# TS1A.net
KiCad netlist of a schematic drawn in Altium Designer
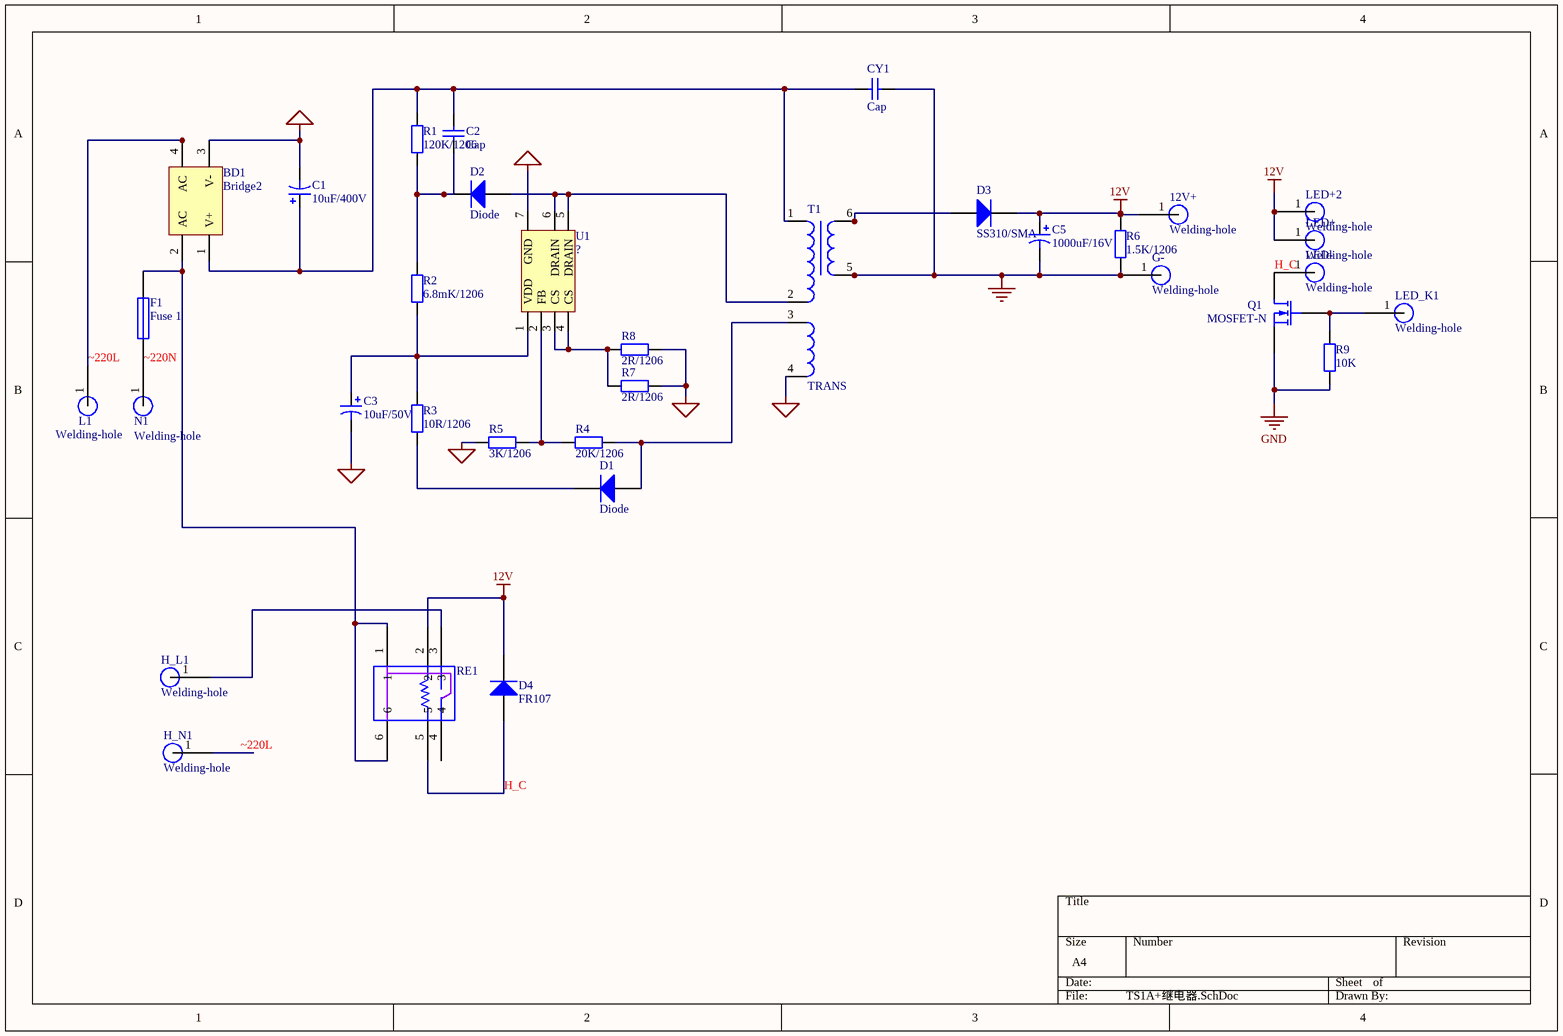
[diagram p0: TS1A+继电器.SchDoc]

(export (version "E")
  (design (tool "Eeschema 10.0.6"))
  (components
    (comp (ref "12V+")
      (value "Welding-hole")
      (footprint "PAD")
      (description "焊接点")
      (libsource (lib "TS_2A") (part "Welding-hole"))
    )
    (comp (ref "BD1")
      (value "Bridge2")
      (footprint "MBL10S")
      (description "Diode Bridge")
      (fields (field (name "PUBLISHER") "Altium Limited"))
      (libsource (lib "Miscellaneous Devices") (part "Bridge2"))
    )
    (comp (ref "C1")
      (value "10uF/400V")
      (footprint "400V/10uF 直插电解电容")
      (description "直插电解电容15uF/400V")
      (fields (field (name "PUBLISHER") "Altium Limited"))
      (libsource (lib "Miscellaneous Devices") (part "Cap Pol1"))
    )
    (comp (ref "C2")
      (value "Cap")
      (footprint "C1206")
      (description "Capacitor")
      (fields (field (name "PUBLISHER") "Altium Limited"))
      (libsource (lib "Miscellaneous Devices") (part "Cap"))
    )
    (comp (ref "C3")
      (value "10uF/50V")
      (footprint "50V/10uF")
      (description "直插电解电容15uF/400V")
      (fields (field (name "PUBLISHER") "Altium Limited"))
      (libsource (lib "Miscellaneous Devices") (part "Cap Pol1"))
    )
    (comp (ref "C5")
      (value "1000uF/16V")
      (footprint "16V/680uF")
      (description "直插电解电容15uF/400V")
      (fields (field (name "PUBLISHER") "Altium Limited"))
      (libsource (lib "Miscellaneous Devices") (part "Cap Pol1"))
    )
    (comp (ref "CY1")
      (value "Cap")
      (footprint "C1206")
      (description "Capacitor")
      (fields (field (name "PUBLISHER") "Altium Limited"))
      (libsource (lib "Miscellaneous Devices") (part "Cap"))
    )
    (comp (ref "D1")
      (value "Diode")
      (footprint "SOD123")
      (description "Default Diode")
      (fields (field (name "PUBLISHER") "Altium Limited"))
      (libsource (lib "Miscellaneous Devices") (part "Diode"))
    )
    (comp (ref "D2")
      (value "Diode")
      (footprint "SOD123")
      (description "Default Diode")
      (fields (field (name "PUBLISHER") "Altium Limited"))
      (libsource (lib "Miscellaneous Devices") (part "Diode"))
    )
    (comp (ref "D3")
      (value "SS310/SMA")
      (footprint "SMA")
      (fields (field (name "PUBLISHER") "Altium Limited"))
      (libsource (lib "Miscellaneous Devices") (part "Diode"))
    )
    (comp (ref "D4")
      (value "FR107")
      (footprint "SOD123")
      (description "Default Diode")
      (fields (field (name "PUBLISHER") "Altium Limited"))
      (libsource (lib "Miscellaneous Devices") (part "Diode"))
    )
    (comp (ref "F1")
      (value "Fuse 1")
      (footprint "FUSE")
      (description "保险丝")
      (fields (field (name "PUBLISHER") "Altium Limited"))
      (libsource (lib "Miscellaneous Devices") (part "Fuse 1"))
    )
    (comp (ref "G-")
      (value "Welding-hole")
      (footprint "PAD")
      (description "焊接点")
      (libsource (lib "TS_2A") (part "Welding-hole"))
    )
    (comp (ref "H_L1")
      (value "Welding-hole")
      (footprint "PAD")
      (description "焊接点")
      (libsource (lib "TS_2A") (part "Welding-hole"))
    )
    (comp (ref "H_N1")
      (value "Welding-hole")
      (footprint "PAD")
      (description "焊接点")
      (libsource (lib "TS_2A") (part "Welding-hole"))
    )
    (comp (ref "L1")
      (value "Welding-hole")
      (footprint "PAD")
      (description "焊接点")
      (libsource (lib "TS_2A") (part "Welding-hole"))
    )
    (comp (ref "LED+")
      (value "Welding-hole")
      (footprint "PAD")
      (description "焊接点")
      (libsource (lib "TS_2A") (part "Welding-hole"))
    )
    (comp (ref "LED+2")
      (value "Welding-hole")
      (footprint "PAD")
      (description "焊接点")
      (libsource (lib "TS_2A") (part "Welding-hole"))
    )
    (comp (ref "LED-")
      (value "Welding-hole")
      (footprint "PAD")
      (description "焊接点")
      (libsource (lib "TS_2A") (part "Welding-hole"))
    )
    (comp (ref "LED_K1")
      (value "Welding-hole")
      (footprint "PAD")
      (description "焊接点")
      (libsource (lib "TS_2A") (part "Welding-hole"))
    )
    (comp (ref "N1")
      (value "Welding-hole")
      (footprint "PAD")
      (description "焊接点")
      (libsource (lib "TS_2A") (part "Welding-hole"))
    )
    (comp (ref "Q1")
      (value "MOSFET-N")
      (footprint "SOT_23_N-MOS")
      (description "N-Channel MOSFET")
      (fields (field (name "PUBLISHER") "Altium Limited"))
      (libsource (lib "Miscellaneous Devices") (part "MOSFET-N"))
    )
    (comp (ref "R1")
      (value "120K/1206")
      (footprint "R1206")
      (description "Resistor")
      (fields (field (name "PUBLISHER") "Altium Limited"))
      (libsource (lib "") (part "Res2_2"))
    )
    (comp (ref "R2")
      (value "6.8mK/1206")
      (footprint "R1206")
      (description "Resistor")
      (fields (field (name "PUBLISHER") "Altium Limited"))
      (libsource (lib "") (part "Res2_2"))
    )
    (comp (ref "R3")
      (value "10R/1206")
      (footprint "R1206")
      (description "Resistor")
      (fields (field (name "PUBLISHER") "Altium Limited"))
      (libsource (lib "") (part "Res2_1"))
    )
    (comp (ref "R4")
      (value "20K/1206")
      (footprint "R1206")
      (description "Resistor")
      (fields (field (name "PUBLISHER") "Altium Limited"))
      (libsource (lib "Miscellaneous Devices") (part "Res2"))
    )
    (comp (ref "R5")
      (value "3K/1206")
      (footprint "R1206")
      (description "Resistor")
      (fields (field (name "PUBLISHER") "Altium Limited"))
      (libsource (lib "Miscellaneous Devices") (part "Res2"))
    )
    (comp (ref "R6")
      (value "1.5K/1206")
      (footprint "R1206")
      (description "Resistor")
      (fields (field (name "PUBLISHER") "Altium Limited"))
      (libsource (lib "") (part "Res2_2"))
    )
    (comp (ref "R7")
      (value "2R/1206")
      (footprint "R1206")
      (description "Resistor")
      (fields (field (name "PUBLISHER") "Altium Limited"))
      (libsource (lib "Miscellaneous Devices") (part "Res2"))
    )
    (comp (ref "R8")
      (value "2R/1206")
      (footprint "R1206")
      (description "Resistor")
      (fields (field (name "PUBLISHER") "Altium Limited"))
      (libsource (lib "Miscellaneous Devices") (part "Res2"))
    )
    (comp (ref "R9")
      (value "10K")
      (footprint "R1206")
      (description "Resistor")
      (fields (field (name "PUBLISHER") "Altium Limited"))
      (libsource (lib "") (part "Res2_1"))
    )
    (comp (ref "RE1")
      (value "RELAY-BSZ6-SS-112L")
      (footprint "HKE_HRS1_DC12v")
      (description "RELAY-6P")
      (libsource (lib "Schlib1") (part "RELAY-6P"))
    )
    (comp (ref "T1")
      (value "TRANS")
      (footprint "TRANS_1A")
      (description "变压器")
      (libsource (lib "Schlib1") (part "TRANS"))
    )
    (comp (ref "U1") (value "?") (footprint "SOP-7") (libsource (lib "Schlib1") (part "Component_1")))
  )
  (nets
    (net (code "1") (name "/H_C") (class "Default")
      (node (ref "D4") (pin "1") (pinfunction "A_1") (pintype "passive"))
      (node (ref "LED-") (pin "1") (pinfunction "1_1") (pintype "passive"))
      (node (ref "Q1") (pin "1") (pinfunction "D_1") (pintype "passive"))
      (node (ref "RE1") (pin "5") (pinfunction "5_5") (pintype "passive"))
    )
    (net (code "2") (name "/~220L") (class "Default")
      (node (ref "BD1") (pin "4") (pinfunction "AC_4") (pintype "passive"))
      (node (ref "H_N1") (pin "1") (pinfunction "1_1") (pintype "passive"))
      (node (ref "L1") (pin "1") (pinfunction "1_1") (pintype "passive"))
    )
    (net (code "3") (name "/~220N") (class "Default")
      (node (ref "F1") (pin "1") (pinfunction "1_1") (pintype "passive"))
      (node (ref "N1") (pin "1") (pinfunction "1_1") (pintype "passive"))
    )
    (net (code "4") (name "12V") (class "Default")
      (node (ref "12V+") (pin "1") (pinfunction "1_1") (pintype "passive"))
      (node (ref "C5") (pin "1") (pinfunction "1_1") (pintype "passive"))
      (node (ref "D3") (pin "2") (pinfunction "K_2") (pintype "passive"))
      (node (ref "D4") (pin "2") (pinfunction "K_2") (pintype "passive"))
      (node (ref "LED+") (pin "1") (pinfunction "1_1") (pintype "passive"))
      (node (ref "LED+2") (pin "1") (pinfunction "1_1") (pintype "passive"))
      (node (ref "R6") (pin "2") (pinfunction "2_2") (pintype "passive"))
      (node (ref "RE1") (pin "2") (pinfunction "2_2") (pintype "passive"))
    )
    (net (code "5") (name "AGND") (class "Default")
      (node (ref "BD1") (pin "3") (pinfunction "V-_3") (pintype "passive"))
      (node (ref "C1") (pin "2") (pinfunction "2_2") (pintype "passive"))
      (node (ref "C3") (pin "2") (pinfunction "2_2") (pintype "passive"))
      (node (ref "R5") (pin "1") (pinfunction "1_1") (pintype "passive"))
      (node (ref "R7") (pin "2") (pinfunction "2_2") (pintype "passive"))
      (node (ref "R8") (pin "2") (pinfunction "2_2") (pintype "passive"))
      (node (ref "T1") (pin "4") (pinfunction "5_4") (pintype "passive"))
      (node (ref "U1") (pin "7") (pinfunction "GND_7") (pintype "passive"))
    )
    (net (code "6") (name "GND") (class "Default")
      (node (ref "C5") (pin "2") (pinfunction "2_2") (pintype "passive"))
      (node (ref "CY1") (pin "2") (pinfunction "2_2") (pintype "passive"))
      (node (ref "G-") (pin "1") (pinfunction "1_1") (pintype "passive"))
      (node (ref "Q1") (pin "3") (pinfunction "S_3") (pintype "passive"))
      (node (ref "R6") (pin "1") (pinfunction "1_1") (pintype "passive"))
      (node (ref "R9") (pin "2") (pinfunction "2_2") (pintype "passive"))
      (node (ref "T1") (pin "5") (pinfunction "5_5") (pintype "passive"))
    )
    (net (code "7") (name "Net-(BD1-AC-Pad2)") (class "Default")
      (node (ref "BD1") (pin "2") (pinfunction "AC_2") (pintype "passive"))
      (node (ref "F1") (pin "2") (pinfunction "2_2") (pintype "passive"))
      (node (ref "RE1") (pin "1") (pinfunction "1_1") (pintype "passive"))
      (node (ref "RE1") (pin "6") (pinfunction "6_6") (pintype "passive"))
    )
    (net (code "8") (name "Net-(BD1-V+)") (class "Default")
      (node (ref "BD1") (pin "1") (pinfunction "V+_1") (pintype "passive"))
      (node (ref "C1") (pin "1") (pinfunction "1_1") (pintype "passive"))
      (node (ref "C2") (pin "2") (pinfunction "2_2") (pintype "passive"))
      (node (ref "CY1") (pin "1") (pinfunction "1_1") (pintype "passive"))
      (node (ref "R1") (pin "2") (pinfunction "2_2") (pintype "passive"))
      (node (ref "T1") (pin "1") (pinfunction "1_1") (pintype "passive"))
    )
    (net (code "9") (name "Net-(D1-A)") (class "Default")
      (node (ref "D1") (pin "1") (pinfunction "A_1") (pintype "passive"))
      (node (ref "R4") (pin "2") (pinfunction "2_2") (pintype "passive"))
      (node (ref "T1") (pin "3") (pinfunction "3_3") (pintype "passive"))
    )
    (net (code "10") (name "Net-(D1-K)") (class "Default")
      (node (ref "D1") (pin "2") (pinfunction "K_2") (pintype "passive"))
      (node (ref "R3") (pin "2") (pinfunction "2_2") (pintype "passive"))
    )
    (net (code "11") (name "Net-(D2-A)") (class "Default")
      (node (ref "D2") (pin "1") (pinfunction "A_1") (pintype "passive"))
      (node (ref "T1") (pin "2") (pinfunction "2_2") (pintype "passive"))
      (node (ref "U1") (pin "5") (pinfunction "DRAIN_5") (pintype "passive"))
      (node (ref "U1") (pin "6") (pinfunction "DRAIN_6") (pintype "passive"))
    )
    (net (code "12") (name "Net-(D2-K)") (class "Default")
      (node (ref "C2") (pin "1") (pinfunction "1_1") (pintype "passive"))
      (node (ref "D2") (pin "2") (pinfunction "K_2") (pintype "passive"))
      (node (ref "R1") (pin "1") (pinfunction "1_1") (pintype "passive"))
      (node (ref "R2") (pin "2") (pinfunction "2_2") (pintype "passive"))
    )
    (net (code "13") (name "Net-(D3-A)") (class "Default")
      (node (ref "D3") (pin "1") (pinfunction "A_1") (pintype "passive"))
      (node (ref "T1") (pin "6") (pinfunction "6_6") (pintype "passive"))
    )
    (net (code "14") (name "Net-(H_L1-Pad1)") (class "Default")
      (node (ref "H_L1") (pin "1") (pinfunction "1_1") (pintype "passive"))
      (node (ref "RE1") (pin "3") (pinfunction "3_3") (pintype "passive"))
    )
    (net (code "15") (name "Net-(Q1-G)") (class "Default")
      (node (ref "LED_K1") (pin "1") (pinfunction "1_1") (pintype "passive"))
      (node (ref "Q1") (pin "2") (pinfunction "G_2") (pintype "passive"))
      (node (ref "R9") (pin "1") (pinfunction "1_1") (pintype "passive"))
    )
    (net (code "16") (name "Net-(R7-Pad1)") (class "Default")
      (node (ref "R7") (pin "1") (pinfunction "1_1") (pintype "passive"))
      (node (ref "R8") (pin "1") (pinfunction "1_1") (pintype "passive"))
      (node (ref "U1") (pin "3") (pinfunction "CS_3") (pintype "passive"))
      (node (ref "U1") (pin "4") (pinfunction "CS_4") (pintype "passive"))
    )
    (net (code "17") (name "Net-(U1-FB)") (class "Default")
      (node (ref "R4") (pin "1") (pinfunction "1_1") (pintype "passive"))
      (node (ref "R5") (pin "2") (pinfunction "2_2") (pintype "passive"))
      (node (ref "U1") (pin "2") (pinfunction "FB_2") (pintype "passive"))
    )
    (net (code "18") (name "Net-(U1-VDD)") (class "Default")
      (node (ref "C3") (pin "1") (pinfunction "1_1") (pintype "passive"))
      (node (ref "R2") (pin "1") (pinfunction "1_1") (pintype "passive"))
      (node (ref "R3") (pin "1") (pinfunction "1_1") (pintype "passive"))
      (node (ref "U1") (pin "1") (pinfunction "VDD_1") (pintype "passive"))
    )
    (net (code "19") (name "unconnected-(RE1-Pad4)") (class "Default")
      (node (ref "RE1") (pin "4") (pinfunction "4_4") (pintype "passive"))
    )
  )
)
